# SMALL_EAGLE7.net
KiCad netlist of a schematic drawn in EAGLE
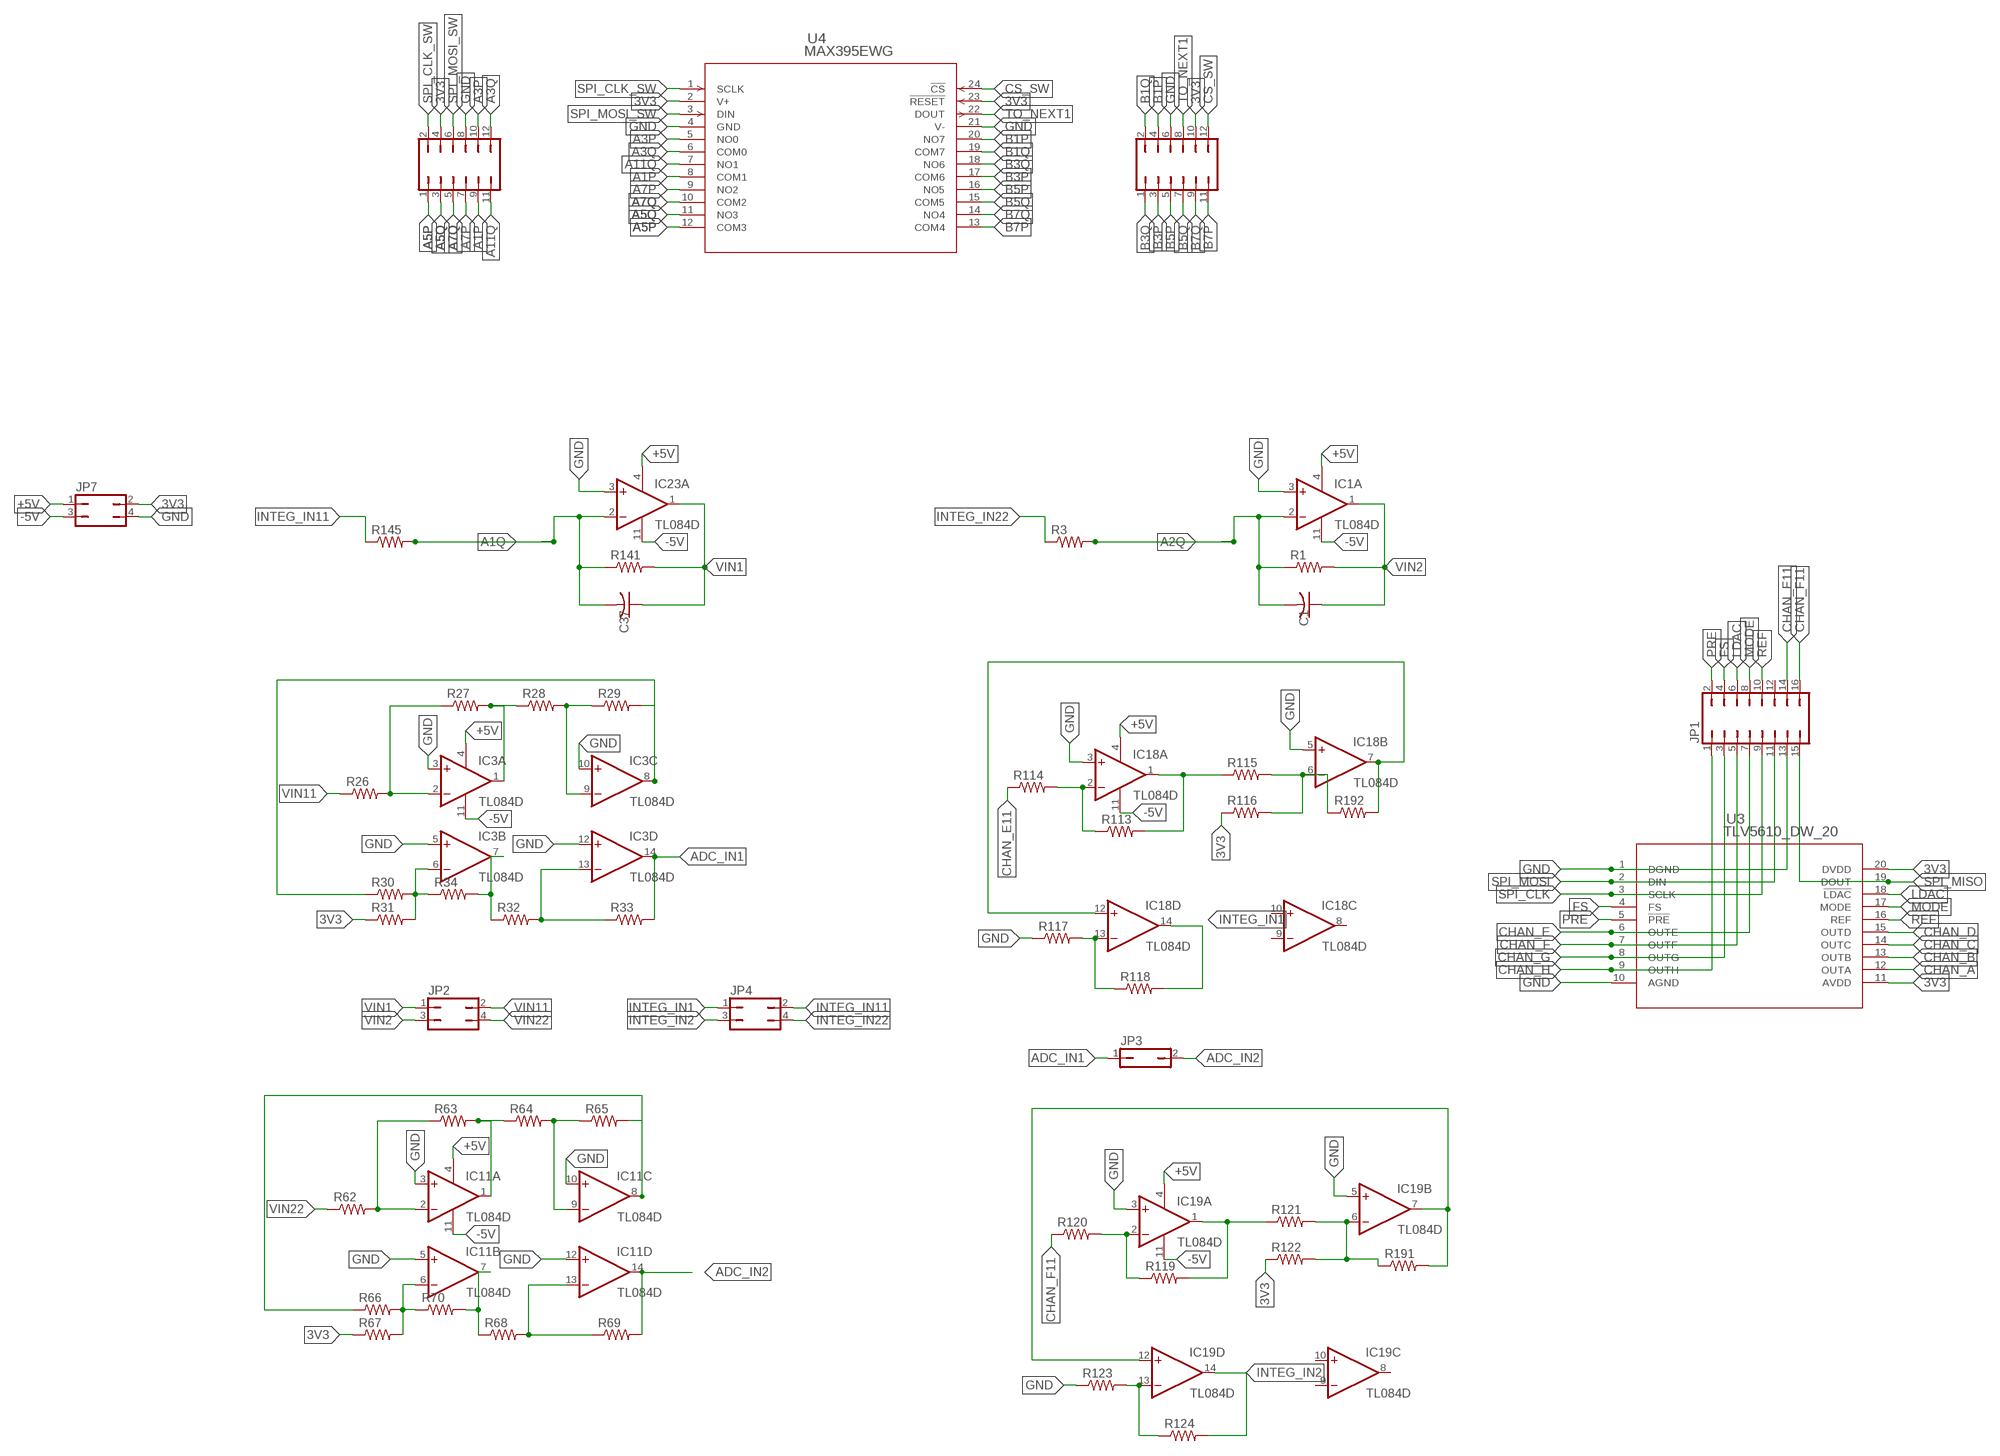
[diagram p0: schematic, sheet 1]

(export (version "E")
  (design (tool "Eeschema 10.0.6"))
  (components
    (comp (ref "C1")
      (value "C-USC1206")
      (footprint "eagle-import:C1206")
      (libsource (lib "eagle-import") (part "C-USC1206"))
    )
    (comp (ref "C37")
      (value "C-USC1206")
      (footprint "eagle-import:C1206")
      (libsource (lib "eagle-import") (part "C-USC1206"))
    )
    (comp (ref "IC1")
      (value "TL084D")
      (footprint "eagle-import:SO14")
      (libsource (lib "eagle-import") (part "TL084D"))
    )
    (comp (ref "IC3")
      (value "TL084D")
      (footprint "eagle-import:SO14")
      (libsource (lib "eagle-import") (part "TL084D"))
    )
    (comp (ref "IC11")
      (value "TL084D")
      (footprint "eagle-import:SO14")
      (libsource (lib "eagle-import") (part "TL084D"))
    )
    (comp (ref "IC18")
      (value "TL084D")
      (footprint "eagle-import:SO14")
      (libsource (lib "eagle-import") (part "TL084D"))
    )
    (comp (ref "IC19")
      (value "TL084D")
      (footprint "eagle-import:SO14")
      (libsource (lib "eagle-import") (part "TL084D"))
    )
    (comp (ref "IC23")
      (value "TL084D")
      (footprint "eagle-import:SO14")
      (libsource (lib "eagle-import") (part "TL084D"))
    )
    (comp (ref "JP1")
      (value "JP8Q")
      (footprint "eagle-import:JP8Q")
      (libsource (lib "eagle-import") (part "JP8Q"))
    )
    (comp (ref "JP2")
      (value "JP2Q")
      (footprint "eagle-import:JP2Q")
      (libsource (lib "eagle-import") (part "JP2Q"))
    )
    (comp (ref "JP3")
      (value "JP1Q")
      (footprint "eagle-import:JP1")
      (libsource (lib "eagle-import") (part "JP1Q"))
    )
    (comp (ref "JP4")
      (value "JP2Q")
      (footprint "eagle-import:JP2Q")
      (libsource (lib "eagle-import") (part "JP2Q"))
    )
    (comp (ref "JP5")
      (value "JP6Q")
      (footprint "eagle-import:JP6Q")
      (libsource (lib "eagle-import") (part "JP6Q"))
    )
    (comp (ref "JP6")
      (value "JP6Q")
      (footprint "eagle-import:JP6Q")
      (libsource (lib "eagle-import") (part "JP6Q"))
    )
    (comp (ref "JP7")
      (value "JP2Q")
      (footprint "eagle-import:JP2Q")
      (libsource (lib "eagle-import") (part "JP2Q"))
    )
    (comp (ref "R1")
      (value "R-US_R1206")
      (footprint "eagle-import:R1206")
      (libsource (lib "eagle-import") (part "R-US_R1206"))
    )
    (comp (ref "R3")
      (value "R-US_R1206")
      (footprint "eagle-import:R1206")
      (libsource (lib "eagle-import") (part "R-US_R1206"))
    )
    (comp (ref "R26")
      (value "R-US_R1206")
      (footprint "eagle-import:R1206")
      (libsource (lib "eagle-import") (part "R-US_R1206"))
    )
    (comp (ref "R27")
      (value "R-US_R1206")
      (footprint "eagle-import:R1206")
      (libsource (lib "eagle-import") (part "R-US_R1206"))
    )
    (comp (ref "R28")
      (value "R-US_R1206")
      (footprint "eagle-import:R1206")
      (libsource (lib "eagle-import") (part "R-US_R1206"))
    )
    (comp (ref "R29")
      (value "R-US_R1206")
      (footprint "eagle-import:R1206")
      (libsource (lib "eagle-import") (part "R-US_R1206"))
    )
    (comp (ref "R30")
      (value "R-US_R1206")
      (footprint "eagle-import:R1206")
      (libsource (lib "eagle-import") (part "R-US_R1206"))
    )
    (comp (ref "R31")
      (value "R-US_R1206")
      (footprint "eagle-import:R1206")
      (libsource (lib "eagle-import") (part "R-US_R1206"))
    )
    (comp (ref "R32")
      (value "R-US_R1206")
      (footprint "eagle-import:R1206")
      (libsource (lib "eagle-import") (part "R-US_R1206"))
    )
    (comp (ref "R33")
      (value "R-US_R1206")
      (footprint "eagle-import:R1206")
      (libsource (lib "eagle-import") (part "R-US_R1206"))
    )
    (comp (ref "R34")
      (value "R-US_R1206")
      (footprint "eagle-import:R1206")
      (libsource (lib "eagle-import") (part "R-US_R1206"))
    )
    (comp (ref "R62")
      (value "R-US_R1206")
      (footprint "eagle-import:R1206")
      (libsource (lib "eagle-import") (part "R-US_R1206"))
    )
    (comp (ref "R63")
      (value "R-US_R1206")
      (footprint "eagle-import:R1206")
      (libsource (lib "eagle-import") (part "R-US_R1206"))
    )
    (comp (ref "R64")
      (value "R-US_R1206")
      (footprint "eagle-import:R1206")
      (libsource (lib "eagle-import") (part "R-US_R1206"))
    )
    (comp (ref "R65")
      (value "R-US_R1206")
      (footprint "eagle-import:R1206")
      (libsource (lib "eagle-import") (part "R-US_R1206"))
    )
    (comp (ref "R66")
      (value "R-US_R1206")
      (footprint "eagle-import:R1206")
      (libsource (lib "eagle-import") (part "R-US_R1206"))
    )
    (comp (ref "R67")
      (value "R-US_R1206")
      (footprint "eagle-import:R1206")
      (libsource (lib "eagle-import") (part "R-US_R1206"))
    )
    (comp (ref "R68")
      (value "R-US_R1206")
      (footprint "eagle-import:R1206")
      (libsource (lib "eagle-import") (part "R-US_R1206"))
    )
    (comp (ref "R69")
      (value "R-US_R1206")
      (footprint "eagle-import:R1206")
      (libsource (lib "eagle-import") (part "R-US_R1206"))
    )
    (comp (ref "R70")
      (value "R-US_R1206")
      (footprint "eagle-import:R1206")
      (libsource (lib "eagle-import") (part "R-US_R1206"))
    )
    (comp (ref "R113")
      (value "R-US_R1206")
      (footprint "eagle-import:R1206")
      (libsource (lib "eagle-import") (part "R-US_R1206"))
    )
    (comp (ref "R114")
      (value "R-US_R1206")
      (footprint "eagle-import:R1206")
      (libsource (lib "eagle-import") (part "R-US_R1206"))
    )
    (comp (ref "R115")
      (value "R-US_R1206")
      (footprint "eagle-import:R1206")
      (libsource (lib "eagle-import") (part "R-US_R1206"))
    )
    (comp (ref "R116")
      (value "R-US_R1206")
      (footprint "eagle-import:R1206")
      (libsource (lib "eagle-import") (part "R-US_R1206"))
    )
    (comp (ref "R117")
      (value "R-US_R1206")
      (footprint "eagle-import:R1206")
      (libsource (lib "eagle-import") (part "R-US_R1206"))
    )
    (comp (ref "R118")
      (value "R-US_R1206")
      (footprint "eagle-import:R1206")
      (libsource (lib "eagle-import") (part "R-US_R1206"))
    )
    (comp (ref "R119")
      (value "R-US_R1206")
      (footprint "eagle-import:R1206")
      (libsource (lib "eagle-import") (part "R-US_R1206"))
    )
    (comp (ref "R120")
      (value "R-US_R1206")
      (footprint "eagle-import:R1206")
      (libsource (lib "eagle-import") (part "R-US_R1206"))
    )
    (comp (ref "R121")
      (value "R-US_R1206")
      (footprint "eagle-import:R1206")
      (libsource (lib "eagle-import") (part "R-US_R1206"))
    )
    (comp (ref "R122")
      (value "R-US_R1206")
      (footprint "eagle-import:R1206")
      (libsource (lib "eagle-import") (part "R-US_R1206"))
    )
    (comp (ref "R123")
      (value "R-US_R1206")
      (footprint "eagle-import:R1206")
      (libsource (lib "eagle-import") (part "R-US_R1206"))
    )
    (comp (ref "R124")
      (value "R-US_R1206")
      (footprint "eagle-import:R1206")
      (libsource (lib "eagle-import") (part "R-US_R1206"))
    )
    (comp (ref "R141")
      (value "R-US_R1206")
      (footprint "eagle-import:R1206")
      (libsource (lib "eagle-import") (part "R-US_R1206"))
    )
    (comp (ref "R145")
      (value "R-US_R1206")
      (footprint "eagle-import:R1206")
      (libsource (lib "eagle-import") (part "R-US_R1206"))
    )
    (comp (ref "R191")
      (value "R-US_R1206")
      (footprint "eagle-import:R1206")
      (libsource (lib "eagle-import") (part "R-US_R1206"))
    )
    (comp (ref "R192")
      (value "R-US_R1206")
      (footprint "eagle-import:R1206")
      (libsource (lib "eagle-import") (part "R-US_R1206"))
    )
    (comp (ref "U3")
      (value "TLV5610_DW_20")
      (footprint "eagle-import:DW20")
      (libsource (lib "eagle-import") (part "TLV5610_DW_20"))
    )
    (comp (ref "U4")
      (value "MAX395EWG")
      (footprint "eagle-import:21-0042B_24")
      (fields (field (name "MANUFACTURER_PART_NUMBER") "max395ewg"))
      (libsource (lib "eagle-import") (part "MAX395EWG"))
    )
  )
  (nets
    (net (code "1") (name "+5V") (class "Default")
      (node (ref "IC1") (pin "4") (pinfunction "V+_4") (pintype "power_in"))
      (node (ref "IC11") (pin "4") (pinfunction "V+_4") (pintype "power_in"))
      (node (ref "IC18") (pin "4") (pinfunction "V+_4") (pintype "power_in"))
      (node (ref "IC19") (pin "4") (pinfunction "V+_4") (pintype "power_in"))
      (node (ref "IC23") (pin "4") (pinfunction "V+_4") (pintype "power_in"))
      (node (ref "IC3") (pin "4") (pinfunction "V+_4") (pintype "power_in"))
      (node (ref "JP7") (pin "1") (pinfunction "1_1") (pintype "passive"))
    )
    (net (code "2") (name "-5V") (class "Default")
      (node (ref "IC1") (pin "11") (pinfunction "V-_11") (pintype "power_in"))
      (node (ref "IC11") (pin "11") (pinfunction "V-_11") (pintype "power_in"))
      (node (ref "IC18") (pin "11") (pinfunction "V-_11") (pintype "power_in"))
      (node (ref "IC19") (pin "11") (pinfunction "V-_11") (pintype "power_in"))
      (node (ref "IC23") (pin "11") (pinfunction "V-_11") (pintype "power_in"))
      (node (ref "IC3") (pin "11") (pinfunction "V-_11") (pintype "power_in"))
      (node (ref "JP7") (pin "3") (pinfunction "3_3") (pintype "passive"))
    )
    (net (code "3") (name "3V3") (class "Default")
      (node (ref "JP5") (pin "4") (pinfunction "4_4") (pintype "passive"))
      (node (ref "JP6") (pin "10") (pinfunction "10_10") (pintype "passive"))
      (node (ref "JP7") (pin "2") (pinfunction "2_2") (pintype "passive"))
      (node (ref "R116") (pin "1") (pinfunction "1_1") (pintype "passive"))
      (node (ref "R122") (pin "1") (pinfunction "1_1") (pintype "passive"))
      (node (ref "R31") (pin "1") (pinfunction "1_1") (pintype "passive"))
      (node (ref "R67") (pin "1") (pinfunction "1_1") (pintype "passive"))
      (node (ref "U3") (pin "11") (pinfunction "AVDD_11") (pintype "power_in"))
      (node (ref "U3") (pin "20") (pinfunction "DVDD_20") (pintype "power_in"))
      (node (ref "U4") (pin "2") (pinfunction "V+_2") (pintype "power_in"))
      (node (ref "U4") (pin "23") (pinfunction "~{RESET}_23") (pintype "input"))
    )
    (net (code "4") (name "A1P") (class "Default")
      (node (ref "JP5") (pin "9") (pinfunction "9_9") (pintype "passive"))
      (node (ref "U4") (pin "8") (pinfunction "COM1_8") (pintype "passive"))
    )
    (net (code "5") (name "A1Q") (class "Default")
      (node (ref "C37") (pin "2") (pinfunction "2_2") (pintype "passive"))
      (node (ref "IC23") (pin "2") (pinfunction "-IN_2") (pintype "input"))
      (node (ref "R141") (pin "1") (pinfunction "1_1") (pintype "passive"))
      (node (ref "R145") (pin "2") (pinfunction "2_2") (pintype "passive"))
    )
    (net (code "6") (name "A2Q") (class "Default")
      (node (ref "C1") (pin "2") (pinfunction "2_2") (pintype "passive"))
      (node (ref "IC1") (pin "2") (pinfunction "-IN_2") (pintype "input"))
      (node (ref "R1") (pin "1") (pinfunction "1_1") (pintype "passive"))
      (node (ref "R3") (pin "2") (pinfunction "2_2") (pintype "passive"))
    )
    (net (code "7") (name "A3P") (class "Default")
      (node (ref "JP5") (pin "10") (pinfunction "10_10") (pintype "passive"))
      (node (ref "U4") (pin "5") (pinfunction "NO0_5") (pintype "passive"))
    )
    (net (code "8") (name "A3Q") (class "Default")
      (node (ref "JP5") (pin "12") (pinfunction "12_12") (pintype "passive"))
      (node (ref "U4") (pin "6") (pinfunction "COM0_6") (pintype "passive"))
    )
    (net (code "9") (name "A5P") (class "Default")
      (node (ref "JP5") (pin "1") (pinfunction "1_1") (pintype "passive"))
      (node (ref "U4") (pin "12") (pinfunction "COM3_12") (pintype "passive"))
    )
    (net (code "10") (name "A5Q") (class "Default")
      (node (ref "JP5") (pin "3") (pinfunction "3_3") (pintype "passive"))
      (node (ref "U4") (pin "11") (pinfunction "NO3_11") (pintype "passive"))
    )
    (net (code "11") (name "A7P") (class "Default")
      (node (ref "JP5") (pin "7") (pinfunction "7_7") (pintype "passive"))
      (node (ref "U4") (pin "9") (pinfunction "NO2_9") (pintype "passive"))
    )
    (net (code "12") (name "A7Q") (class "Default")
      (node (ref "JP5") (pin "5") (pinfunction "5_5") (pintype "passive"))
      (node (ref "U4") (pin "10") (pinfunction "COM2_10") (pintype "passive"))
    )
    (net (code "13") (name "A11Q") (class "Default")
      (node (ref "JP5") (pin "11") (pinfunction "11_11") (pintype "passive"))
      (node (ref "U4") (pin "7") (pinfunction "NO1_7") (pintype "passive"))
    )
    (net (code "14") (name "ADC_IN1") (class "Default")
      (node (ref "IC3") (pin "14") (pinfunction "OUT_14") (pintype "output"))
      (node (ref "JP3") (pin "1") (pinfunction "1_1") (pintype "passive"))
      (node (ref "R33") (pin "2") (pinfunction "2_2") (pintype "passive"))
    )
    (net (code "15") (name "ADC_IN2") (class "Default")
      (node (ref "IC11") (pin "14") (pinfunction "OUT_14") (pintype "output"))
      (node (ref "JP3") (pin "2") (pinfunction "2_2") (pintype "passive"))
      (node (ref "R69") (pin "2") (pinfunction "2_2") (pintype "passive"))
    )
    (net (code "16") (name "B1P") (class "Default")
      (node (ref "JP6") (pin "4") (pinfunction "4_4") (pintype "passive"))
      (node (ref "U4") (pin "20") (pinfunction "NO7_20") (pintype "passive"))
    )
    (net (code "17") (name "B1Q") (class "Default")
      (node (ref "JP6") (pin "2") (pinfunction "2_2") (pintype "passive"))
      (node (ref "U4") (pin "19") (pinfunction "COM7_19") (pintype "passive"))
    )
    (net (code "18") (name "B3P") (class "Default")
      (node (ref "JP6") (pin "3") (pinfunction "3_3") (pintype "passive"))
      (node (ref "U4") (pin "17") (pinfunction "COM6_17") (pintype "passive"))
    )
    (net (code "19") (name "B3Q") (class "Default")
      (node (ref "JP6") (pin "1") (pinfunction "1_1") (pintype "passive"))
      (node (ref "U4") (pin "18") (pinfunction "NO6_18") (pintype "passive"))
    )
    (net (code "20") (name "B5P") (class "Default")
      (node (ref "JP6") (pin "5") (pinfunction "5_5") (pintype "passive"))
      (node (ref "U4") (pin "16") (pinfunction "NO5_16") (pintype "passive"))
    )
    (net (code "21") (name "B5Q") (class "Default")
      (node (ref "JP6") (pin "7") (pinfunction "7_7") (pintype "passive"))
      (node (ref "U4") (pin "15") (pinfunction "COM5_15") (pintype "passive"))
    )
    (net (code "22") (name "B7P") (class "Default")
      (node (ref "JP6") (pin "11") (pinfunction "11_11") (pintype "passive"))
      (node (ref "U4") (pin "13") (pinfunction "COM4_13") (pintype "passive"))
    )
    (net (code "23") (name "B7Q") (class "Default")
      (node (ref "JP6") (pin "9") (pinfunction "9_9") (pintype "passive"))
      (node (ref "U4") (pin "14") (pinfunction "NO4_14") (pintype "passive"))
    )
    (net (code "24") (name "CHAN_A") (class "Default")
      (node (ref "U3") (pin "12") (pinfunction "OUTA_12") (pintype "output"))
    )
    (net (code "25") (name "CHAN_B") (class "Default")
      (node (ref "U3") (pin "13") (pinfunction "OUTB_13") (pintype "output"))
    )
    (net (code "26") (name "CHAN_C") (class "Default")
      (node (ref "U3") (pin "14") (pinfunction "OUTC_14") (pintype "output"))
    )
    (net (code "27") (name "CHAN_D") (class "Default")
      (node (ref "U3") (pin "15") (pinfunction "OUTD_15") (pintype "output"))
    )
    (net (code "28") (name "CHAN_E") (class "Default")
      (node (ref "JP1") (pin "7") (pinfunction "7_7") (pintype "passive"))
      (node (ref "U3") (pin "6") (pinfunction "OUTE_6") (pintype "output"))
    )
    (net (code "29") (name "CHAN_E11") (class "Default")
      (node (ref "JP1") (pin "14") (pinfunction "14_14") (pintype "passive"))
      (node (ref "R114") (pin "1") (pinfunction "1_1") (pintype "passive"))
    )
    (net (code "30") (name "CHAN_F") (class "Default")
      (node (ref "JP1") (pin "5") (pinfunction "5_5") (pintype "passive"))
      (node (ref "U3") (pin "7") (pinfunction "OUTF_7") (pintype "output"))
    )
    (net (code "31") (name "CHAN_F11") (class "Default")
      (node (ref "JP1") (pin "16") (pinfunction "16_16") (pintype "passive"))
      (node (ref "R120") (pin "1") (pinfunction "1_1") (pintype "passive"))
    )
    (net (code "32") (name "CHAN_G") (class "Default")
      (node (ref "JP1") (pin "3") (pinfunction "3_3") (pintype "passive"))
      (node (ref "U3") (pin "8") (pinfunction "OUTG_8") (pintype "output"))
    )
    (net (code "33") (name "CHAN_H") (class "Default")
      (node (ref "JP1") (pin "1") (pinfunction "1_1") (pintype "passive"))
      (node (ref "U3") (pin "9") (pinfunction "OUTH_9") (pintype "output"))
    )
    (net (code "34") (name "CS_SW") (class "Default")
      (node (ref "JP6") (pin "12") (pinfunction "12_12") (pintype "passive"))
      (node (ref "U4") (pin "24") (pinfunction "~{CS}_24") (pintype "input"))
    )
    (net (code "35") (name "FS") (class "Default")
      (node (ref "JP1") (pin "4") (pinfunction "4_4") (pintype "passive"))
      (node (ref "U3") (pin "4") (pinfunction "FS_4") (pintype "input"))
    )
    (net (code "36") (name "GND") (class "Default")
      (node (ref "IC1") (pin "3") (pinfunction "+IN_3") (pintype "input"))
      (node (ref "IC11") (pin "10") (pinfunction "+IN_10") (pintype "input"))
      (node (ref "IC11") (pin "12") (pinfunction "+IN_12") (pintype "input"))
      (node (ref "IC11") (pin "3") (pinfunction "+IN_3") (pintype "input"))
      (node (ref "IC11") (pin "5") (pinfunction "+IN_5") (pintype "input"))
      (node (ref "IC18") (pin "3") (pinfunction "+IN_3") (pintype "input"))
      (node (ref "IC18") (pin "5") (pinfunction "+IN_5") (pintype "input"))
      (node (ref "IC19") (pin "3") (pinfunction "+IN_3") (pintype "input"))
      (node (ref "IC19") (pin "5") (pinfunction "+IN_5") (pintype "input"))
      (node (ref "IC23") (pin "3") (pinfunction "+IN_3") (pintype "input"))
      (node (ref "IC3") (pin "10") (pinfunction "+IN_10") (pintype "input"))
      (node (ref "IC3") (pin "12") (pinfunction "+IN_12") (pintype "input"))
      (node (ref "IC3") (pin "3") (pinfunction "+IN_3") (pintype "input"))
      (node (ref "IC3") (pin "5") (pinfunction "+IN_5") (pintype "input"))
      (node (ref "JP1") (pin "13") (pinfunction "13_13") (pintype "passive"))
      (node (ref "JP5") (pin "8") (pinfunction "8_8") (pintype "passive"))
      (node (ref "JP6") (pin "6") (pinfunction "6_6") (pintype "passive"))
      (node (ref "JP7") (pin "4") (pinfunction "4_4") (pintype "passive"))
      (node (ref "R117") (pin "1") (pinfunction "1_1") (pintype "passive"))
      (node (ref "R123") (pin "1") (pinfunction "1_1") (pintype "passive"))
      (node (ref "U3") (pin "1") (pinfunction "DGND_1") (pintype "power_in"))
      (node (ref "U3") (pin "10") (pinfunction "AGND_10") (pintype "power_in"))
      (node (ref "U4") (pin "21") (pinfunction "V-_21") (pintype "power_in"))
      (node (ref "U4") (pin "4") (pinfunction "GND_4") (pintype "power_in"))
    )
    (net (code "37") (name "INTEG_IN1") (class "Default")
      (node (ref "IC18") (pin "14") (pinfunction "OUT_14") (pintype "output"))
      (node (ref "JP4") (pin "1") (pinfunction "1_1") (pintype "passive"))
      (node (ref "R118") (pin "2") (pinfunction "2_2") (pintype "passive"))
    )
    (net (code "38") (name "INTEG_IN2") (class "Default")
      (node (ref "IC19") (pin "14") (pinfunction "OUT_14") (pintype "output"))
      (node (ref "JP4") (pin "3") (pinfunction "3_3") (pintype "passive"))
      (node (ref "R124") (pin "2") (pinfunction "2_2") (pintype "passive"))
    )
    (net (code "39") (name "INTEG_IN11") (class "Default")
      (node (ref "JP4") (pin "2") (pinfunction "2_2") (pintype "passive"))
      (node (ref "R145") (pin "1") (pinfunction "1_1") (pintype "passive"))
    )
    (net (code "40") (name "INTEG_IN22") (class "Default")
      (node (ref "JP4") (pin "4") (pinfunction "4_4") (pintype "passive"))
      (node (ref "R3") (pin "1") (pinfunction "1_1") (pintype "passive"))
    )
    (net (code "41") (name "LDAC") (class "Default")
      (node (ref "JP1") (pin "6") (pinfunction "6_6") (pintype "passive"))
      (node (ref "U3") (pin "18") (pinfunction "~{LDAC}_18") (pintype "input"))
    )
    (net (code "42") (name "MODE") (class "Default")
      (node (ref "JP1") (pin "8") (pinfunction "8_8") (pintype "passive"))
      (node (ref "U3") (pin "17") (pinfunction "MODE_17") (pintype "input"))
    )
    (net (code "43") (name "Net-(IC3A--IN)") (class "Default")
      (node (ref "IC3") (pin "2") (pinfunction "-IN_2") (pintype "input"))
      (node (ref "R26") (pin "2") (pinfunction "2_2") (pintype "passive"))
      (node (ref "R27") (pin "1") (pinfunction "1_1") (pintype "passive"))
    )
    (net (code "44") (name "Net-(IC3A-OUT)") (class "Default")
      (node (ref "IC3") (pin "1") (pinfunction "OUT_1") (pintype "output"))
      (node (ref "R27") (pin "2") (pinfunction "2_2") (pintype "passive"))
      (node (ref "R28") (pin "1") (pinfunction "1_1") (pintype "passive"))
    )
    (net (code "45") (name "Net-(IC3B--IN)") (class "Default")
      (node (ref "IC3") (pin "6") (pinfunction "-IN_6") (pintype "input"))
      (node (ref "R30") (pin "2") (pinfunction "2_2") (pintype "passive"))
      (node (ref "R31") (pin "2") (pinfunction "2_2") (pintype "passive"))
      (node (ref "R34") (pin "1") (pinfunction "1_1") (pintype "passive"))
    )
    (net (code "46") (name "Net-(IC3B-OUT)") (class "Default")
      (node (ref "IC3") (pin "7") (pinfunction "OUT_7") (pintype "output"))
      (node (ref "R32") (pin "1") (pinfunction "1_1") (pintype "passive"))
      (node (ref "R34") (pin "2") (pinfunction "2_2") (pintype "passive"))
    )
    (net (code "47") (name "Net-(IC3C--IN)") (class "Default")
      (node (ref "IC3") (pin "9") (pinfunction "-IN_9") (pintype "input"))
      (node (ref "R28") (pin "2") (pinfunction "2_2") (pintype "passive"))
      (node (ref "R29") (pin "1") (pinfunction "1_1") (pintype "passive"))
    )
    (net (code "48") (name "Net-(IC3C-OUT)") (class "Default")
      (node (ref "IC3") (pin "8") (pinfunction "OUT_8") (pintype "output"))
      (node (ref "R29") (pin "2") (pinfunction "2_2") (pintype "passive"))
      (node (ref "R30") (pin "1") (pinfunction "1_1") (pintype "passive"))
    )
    (net (code "49") (name "Net-(IC3D--IN)") (class "Default")
      (node (ref "IC3") (pin "13") (pinfunction "-IN_13") (pintype "input"))
      (node (ref "R32") (pin "2") (pinfunction "2_2") (pintype "passive"))
      (node (ref "R33") (pin "1") (pinfunction "1_1") (pintype "passive"))
    )
    (net (code "50") (name "Net-(IC11A--IN)") (class "Default")
      (node (ref "IC11") (pin "2") (pinfunction "-IN_2") (pintype "input"))
      (node (ref "R62") (pin "2") (pinfunction "2_2") (pintype "passive"))
      (node (ref "R63") (pin "1") (pinfunction "1_1") (pintype "passive"))
    )
    (net (code "51") (name "Net-(IC11A-OUT)") (class "Default")
      (node (ref "IC11") (pin "1") (pinfunction "OUT_1") (pintype "output"))
      (node (ref "R63") (pin "2") (pinfunction "2_2") (pintype "passive"))
      (node (ref "R64") (pin "1") (pinfunction "1_1") (pintype "passive"))
    )
    (net (code "52") (name "Net-(IC11B--IN)") (class "Default")
      (node (ref "IC11") (pin "6") (pinfunction "-IN_6") (pintype "input"))
      (node (ref "R66") (pin "2") (pinfunction "2_2") (pintype "passive"))
      (node (ref "R67") (pin "2") (pinfunction "2_2") (pintype "passive"))
      (node (ref "R70") (pin "1") (pinfunction "1_1") (pintype "passive"))
    )
    (net (code "53") (name "Net-(IC11B-OUT)") (class "Default")
      (node (ref "IC11") (pin "7") (pinfunction "OUT_7") (pintype "output"))
      (node (ref "R68") (pin "1") (pinfunction "1_1") (pintype "passive"))
      (node (ref "R70") (pin "2") (pinfunction "2_2") (pintype "passive"))
    )
    (net (code "54") (name "Net-(IC11C--IN)") (class "Default")
      (node (ref "IC11") (pin "9") (pinfunction "-IN_9") (pintype "input"))
      (node (ref "R64") (pin "2") (pinfunction "2_2") (pintype "passive"))
      (node (ref "R65") (pin "1") (pinfunction "1_1") (pintype "passive"))
    )
    (net (code "55") (name "Net-(IC11C-OUT)") (class "Default")
      (node (ref "IC11") (pin "8") (pinfunction "OUT_8") (pintype "output"))
      (node (ref "R65") (pin "2") (pinfunction "2_2") (pintype "passive"))
      (node (ref "R66") (pin "1") (pinfunction "1_1") (pintype "passive"))
    )
    (net (code "56") (name "Net-(IC11D--IN)") (class "Default")
      (node (ref "IC11") (pin "13") (pinfunction "-IN_13") (pintype "input"))
      (node (ref "R68") (pin "2") (pinfunction "2_2") (pintype "passive"))
      (node (ref "R69") (pin "1") (pinfunction "1_1") (pintype "passive"))
    )
    (net (code "57") (name "Net-(IC18A--IN)") (class "Default")
      (node (ref "IC18") (pin "2") (pinfunction "-IN_2") (pintype "input"))
      (node (ref "R113") (pin "1") (pinfunction "1_1") (pintype "passive"))
      (node (ref "R114") (pin "2") (pinfunction "2_2") (pintype "passive"))
    )
    (net (code "58") (name "Net-(IC18A-OUT)") (class "Default")
      (node (ref "IC18") (pin "1") (pinfunction "OUT_1") (pintype "output"))
      (node (ref "R113") (pin "2") (pinfunction "2_2") (pintype "passive"))
      (node (ref "R115") (pin "1") (pinfunction "1_1") (pintype "passive"))
    )
    (net (code "59") (name "Net-(IC18B--IN)") (class "Default")
      (node (ref "IC18") (pin "6") (pinfunction "-IN_6") (pintype "input"))
      (node (ref "R115") (pin "2") (pinfunction "2_2") (pintype "passive"))
      (node (ref "R116") (pin "2") (pinfunction "2_2") (pintype "passive"))
      (node (ref "R192") (pin "1") (pinfunction "1_1") (pintype "passive"))
    )
    (net (code "60") (name "Net-(IC18B-OUT)") (class "Default")
      (node (ref "IC18") (pin "12") (pinfunction "+IN_12") (pintype "input"))
      (node (ref "IC18") (pin "7") (pinfunction "OUT_7") (pintype "output"))
      (node (ref "R192") (pin "2") (pinfunction "2_2") (pintype "passive"))
    )
    (net (code "61") (name "Net-(IC18D--IN)") (class "Default")
      (node (ref "IC18") (pin "13") (pinfunction "-IN_13") (pintype "input"))
      (node (ref "R117") (pin "2") (pinfunction "2_2") (pintype "passive"))
      (node (ref "R118") (pin "1") (pinfunction "1_1") (pintype "passive"))
    )
    (net (code "62") (name "Net-(IC19A--IN)") (class "Default")
      (node (ref "IC19") (pin "2") (pinfunction "-IN_2") (pintype "input"))
      (node (ref "R119") (pin "1") (pinfunction "1_1") (pintype "passive"))
      (node (ref "R120") (pin "2") (pinfunction "2_2") (pintype "passive"))
    )
    (net (code "63") (name "Net-(IC19A-OUT)") (class "Default")
      (node (ref "IC19") (pin "1") (pinfunction "OUT_1") (pintype "output"))
      (node (ref "R119") (pin "2") (pinfunction "2_2") (pintype "passive"))
      (node (ref "R121") (pin "1") (pinfunction "1_1") (pintype "passive"))
    )
    (net (code "64") (name "Net-(IC19B--IN)") (class "Default")
      (node (ref "IC19") (pin "6") (pinfunction "-IN_6") (pintype "input"))
      (node (ref "R121") (pin "2") (pinfunction "2_2") (pintype "passive"))
      (node (ref "R122") (pin "2") (pinfunction "2_2") (pintype "passive"))
      (node (ref "R191") (pin "1") (pinfunction "1_1") (pintype "passive"))
    )
    (net (code "65") (name "Net-(IC19B-OUT)") (class "Default")
      (node (ref "IC19") (pin "12") (pinfunction "+IN_12") (pintype "input"))
      (node (ref "IC19") (pin "7") (pinfunction "OUT_7") (pintype "output"))
      (node (ref "R191") (pin "2") (pinfunction "2_2") (pintype "passive"))
    )
    (net (code "66") (name "Net-(IC19D--IN)") (class "Default")
      (node (ref "IC19") (pin "13") (pinfunction "-IN_13") (pintype "input"))
      (node (ref "R123") (pin "2") (pinfunction "2_2") (pintype "passive"))
      (node (ref "R124") (pin "1") (pinfunction "1_1") (pintype "passive"))
    )
    (net (code "67") (name "PRE") (class "Default")
      (node (ref "JP1") (pin "2") (pinfunction "2_2") (pintype "passive"))
      (node (ref "U3") (pin "5") (pinfunction "~{PRE}_5") (pintype "input"))
    )
    (net (code "68") (name "REF") (class "Default")
      (node (ref "JP1") (pin "10") (pinfunction "10_10") (pintype "passive"))
      (node (ref "U3") (pin "16") (pinfunction "REF_16") (pintype "input"))
    )
    (net (code "69") (name "SPI_CLK") (class "Default")
      (node (ref "JP1") (pin "9") (pinfunction "9_9") (pintype "passive"))
      (node (ref "U3") (pin "3") (pinfunction "SCLK_3") (pintype "input"))
    )
    (net (code "70") (name "SPI_CLK_SW") (class "Default")
      (node (ref "JP5") (pin "2") (pinfunction "2_2") (pintype "passive"))
      (node (ref "U4") (pin "1") (pinfunction "SCLK_1") (pintype "input"))
    )
    (net (code "71") (name "SPI_MISO") (class "Default")
      (node (ref "JP1") (pin "15") (pinfunction "15_15") (pintype "passive"))
      (node (ref "U3") (pin "19") (pinfunction "DOUT_19") (pintype "output"))
    )
    (net (code "72") (name "SPI_MOSI") (class "Default")
      (node (ref "JP1") (pin "11") (pinfunction "11_11") (pintype "passive"))
      (node (ref "U3") (pin "2") (pinfunction "DIN_2") (pintype "input"))
    )
    (net (code "73") (name "SPI_MOSI_SW") (class "Default")
      (node (ref "JP5") (pin "6") (pinfunction "6_6") (pintype "passive"))
      (node (ref "U4") (pin "3") (pinfunction "DIN_3") (pintype "input"))
    )
    (net (code "74") (name "TO_NEXT1") (class "Default")
      (node (ref "JP6") (pin "8") (pinfunction "8_8") (pintype "passive"))
      (node (ref "U4") (pin "22") (pinfunction "DOUT_22") (pintype "output"))
    )
    (net (code "75") (name "VIN1") (class "Default")
      (node (ref "C37") (pin "1") (pinfunction "1_1") (pintype "passive"))
      (node (ref "IC23") (pin "1") (pinfunction "OUT_1") (pintype "output"))
      (node (ref "JP2") (pin "1") (pinfunction "1_1") (pintype "passive"))
      (node (ref "R141") (pin "2") (pinfunction "2_2") (pintype "passive"))
    )
    (net (code "76") (name "VIN2") (class "Default")
      (node (ref "C1") (pin "1") (pinfunction "1_1") (pintype "passive"))
      (node (ref "IC1") (pin "1") (pinfunction "OUT_1") (pintype "output"))
      (node (ref "JP2") (pin "3") (pinfunction "3_3") (pintype "passive"))
      (node (ref "R1") (pin "2") (pinfunction "2_2") (pintype "passive"))
    )
    (net (code "77") (name "VIN11") (class "Default")
      (node (ref "JP2") (pin "2") (pinfunction "2_2") (pintype "passive"))
      (node (ref "R26") (pin "1") (pinfunction "1_1") (pintype "passive"))
    )
    (net (code "78") (name "VIN22") (class "Default")
      (node (ref "JP2") (pin "4") (pinfunction "4_4") (pintype "passive"))
      (node (ref "R62") (pin "1") (pinfunction "1_1") (pintype "passive"))
    )
    (net (code "79") (name "unconnected-(IC18C-+IN-Pad10)") (class "Default")
      (node (ref "IC18") (pin "10") (pinfunction "+IN_10") (pintype "input"))
    )
    (net (code "80") (name "unconnected-(IC18C--IN-Pad9)") (class "Default")
      (node (ref "IC18") (pin "9") (pinfunction "-IN_9") (pintype "input"))
    )
    (net (code "81") (name "unconnected-(IC18C-OUT-Pad8)") (class "Default")
      (node (ref "IC18") (pin "8") (pinfunction "OUT_8") (pintype "output"))
    )
    (net (code "82") (name "unconnected-(IC19C-+IN-Pad10)") (class "Default")
      (node (ref "IC19") (pin "10") (pinfunction "+IN_10") (pintype "input"))
    )
    (net (code "83") (name "unconnected-(IC19C--IN-Pad9)") (class "Default")
      (node (ref "IC19") (pin "9") (pinfunction "-IN_9") (pintype "input"))
    )
    (net (code "84") (name "unconnected-(IC19C-OUT-Pad8)") (class "Default")
      (node (ref "IC19") (pin "8") (pinfunction "OUT_8") (pintype "output"))
    )
    (net (code "85") (name "unconnected-(JP1-Pad12)") (class "Default")
      (node (ref "JP1") (pin "12") (pinfunction "12_12") (pintype "passive"))
    )
  )
)
